# SCH_SEGEMENTOS.net
KiCad netlist of a schematic drawn in Altium Designer
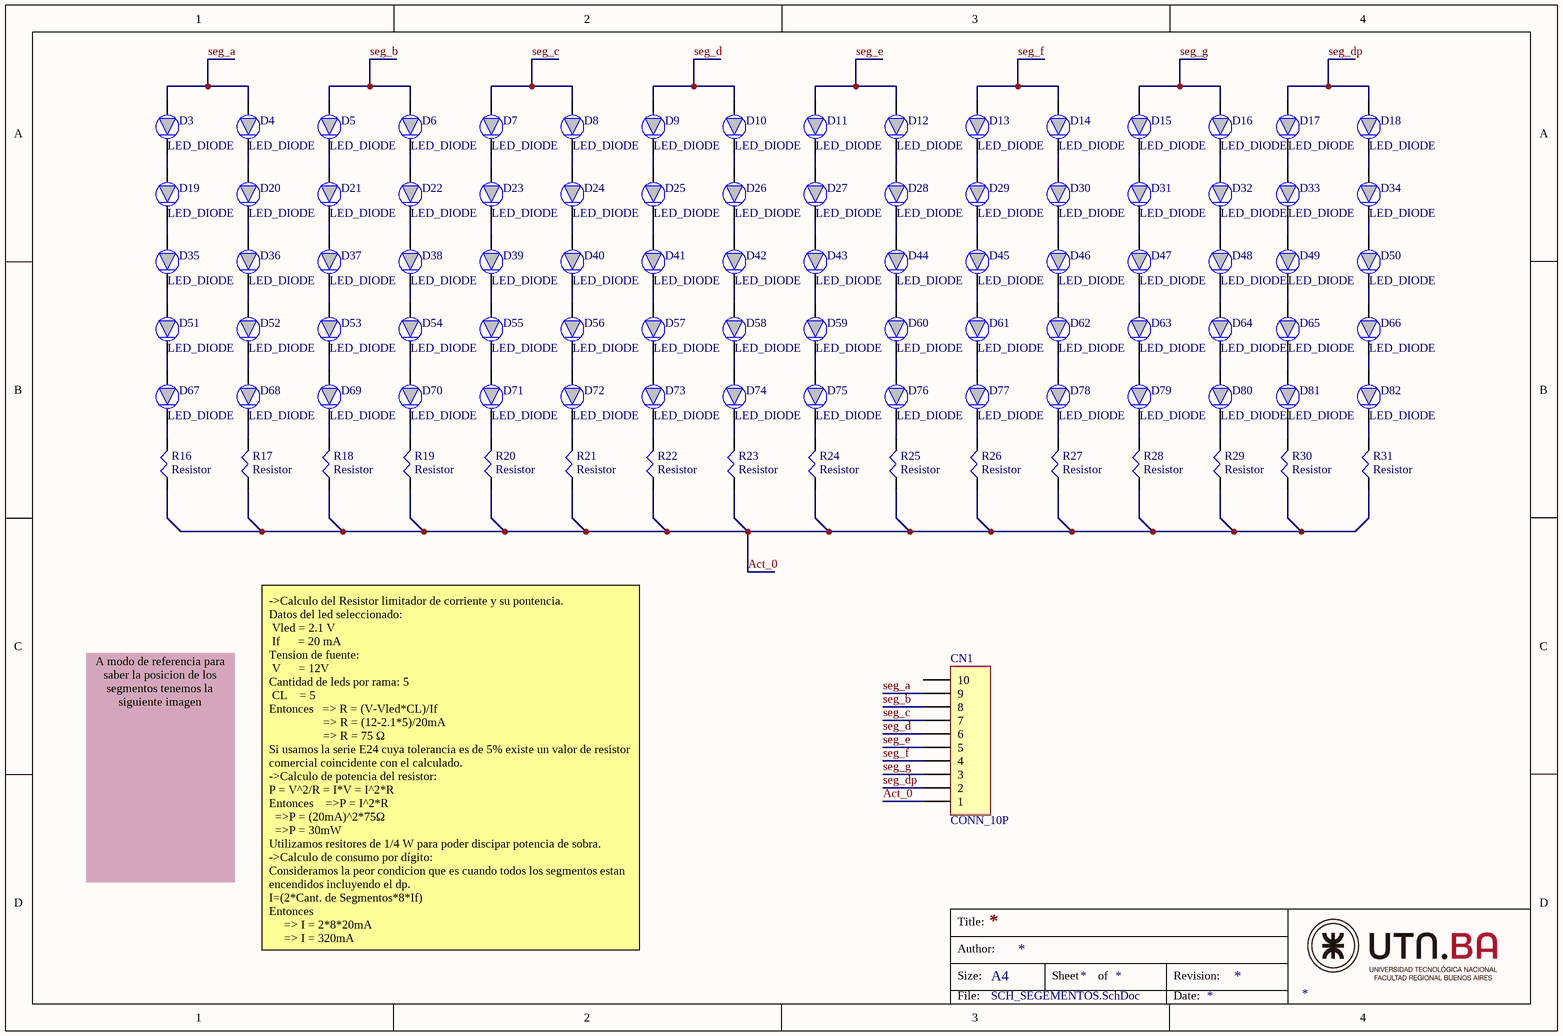
[diagram p0: SCH_SEGEMENTOS.SchDoc]

(export (version "E")
  (design (tool "Eeschema 10.0.6"))
  (components
    (comp (ref "CN1")
      (value "CONN_10P")
      (description "Connector Generic 10 Vias")
      (libsource (lib "SCH_LIB") (part "CONN_10P"))
    )
    (comp (ref "D3")
      (value "LED_DIODE")
      (description "LED rojo 0805")
      (libsource (lib "SCH_LIB") (part "LED_DIODE"))
    )
    (comp (ref "D4")
      (value "LED_DIODE")
      (description "LED rojo 0805")
      (libsource (lib "SCH_LIB") (part "LED_DIODE"))
    )
    (comp (ref "D5")
      (value "LED_DIODE")
      (description "LED rojo 0805")
      (libsource (lib "SCH_LIB") (part "LED_DIODE"))
    )
    (comp (ref "D6")
      (value "LED_DIODE")
      (description "LED rojo 0805")
      (libsource (lib "SCH_LIB") (part "LED_DIODE"))
    )
    (comp (ref "D7")
      (value "LED_DIODE")
      (description "LED rojo 0805")
      (libsource (lib "SCH_LIB") (part "LED_DIODE"))
    )
    (comp (ref "D8")
      (value "LED_DIODE")
      (description "LED rojo 0805")
      (libsource (lib "SCH_LIB") (part "LED_DIODE"))
    )
    (comp (ref "D9")
      (value "LED_DIODE")
      (description "LED rojo 0805")
      (libsource (lib "SCH_LIB") (part "LED_DIODE"))
    )
    (comp (ref "D10")
      (value "LED_DIODE")
      (description "LED rojo 0805")
      (libsource (lib "SCH_LIB") (part "LED_DIODE"))
    )
    (comp (ref "D11")
      (value "LED_DIODE")
      (description "LED rojo 0805")
      (libsource (lib "SCH_LIB") (part "LED_DIODE"))
    )
    (comp (ref "D12")
      (value "LED_DIODE")
      (description "LED rojo 0805")
      (libsource (lib "SCH_LIB") (part "LED_DIODE"))
    )
    (comp (ref "D13")
      (value "LED_DIODE")
      (description "LED rojo 0805")
      (libsource (lib "SCH_LIB") (part "LED_DIODE"))
    )
    (comp (ref "D14")
      (value "LED_DIODE")
      (description "LED rojo 0805")
      (libsource (lib "SCH_LIB") (part "LED_DIODE"))
    )
    (comp (ref "D15")
      (value "LED_DIODE")
      (description "LED rojo 0805")
      (libsource (lib "SCH_LIB") (part "LED_DIODE"))
    )
    (comp (ref "D16")
      (value "LED_DIODE")
      (description "LED rojo 0805")
      (libsource (lib "SCH_LIB") (part "LED_DIODE"))
    )
    (comp (ref "D17")
      (value "LED_DIODE")
      (description "LED rojo 0805")
      (libsource (lib "SCH_LIB") (part "LED_DIODE"))
    )
    (comp (ref "D18")
      (value "LED_DIODE")
      (description "LED rojo 0805")
      (libsource (lib "SCH_LIB") (part "LED_DIODE"))
    )
    (comp (ref "D19")
      (value "LED_DIODE")
      (description "LED rojo 0805")
      (libsource (lib "SCH_LIB") (part "LED_DIODE"))
    )
    (comp (ref "D20")
      (value "LED_DIODE")
      (description "LED rojo 0805")
      (libsource (lib "SCH_LIB") (part "LED_DIODE"))
    )
    (comp (ref "D21")
      (value "LED_DIODE")
      (description "LED rojo 0805")
      (libsource (lib "SCH_LIB") (part "LED_DIODE"))
    )
    (comp (ref "D22")
      (value "LED_DIODE")
      (description "LED rojo 0805")
      (libsource (lib "SCH_LIB") (part "LED_DIODE"))
    )
    (comp (ref "D23")
      (value "LED_DIODE")
      (description "LED rojo 0805")
      (libsource (lib "SCH_LIB") (part "LED_DIODE"))
    )
    (comp (ref "D24")
      (value "LED_DIODE")
      (description "LED rojo 0805")
      (libsource (lib "SCH_LIB") (part "LED_DIODE"))
    )
    (comp (ref "D25")
      (value "LED_DIODE")
      (description "LED rojo 0805")
      (libsource (lib "SCH_LIB") (part "LED_DIODE"))
    )
    (comp (ref "D26")
      (value "LED_DIODE")
      (description "LED rojo 0805")
      (libsource (lib "SCH_LIB") (part "LED_DIODE"))
    )
    (comp (ref "D27")
      (value "LED_DIODE")
      (description "LED rojo 0805")
      (libsource (lib "SCH_LIB") (part "LED_DIODE"))
    )
    (comp (ref "D28")
      (value "LED_DIODE")
      (description "LED rojo 0805")
      (libsource (lib "SCH_LIB") (part "LED_DIODE"))
    )
    (comp (ref "D29")
      (value "LED_DIODE")
      (description "LED rojo 0805")
      (libsource (lib "SCH_LIB") (part "LED_DIODE"))
    )
    (comp (ref "D30")
      (value "LED_DIODE")
      (description "LED rojo 0805")
      (libsource (lib "SCH_LIB") (part "LED_DIODE"))
    )
    (comp (ref "D31")
      (value "LED_DIODE")
      (description "LED rojo 0805")
      (libsource (lib "SCH_LIB") (part "LED_DIODE"))
    )
    (comp (ref "D32")
      (value "LED_DIODE")
      (description "LED rojo 0805")
      (libsource (lib "SCH_LIB") (part "LED_DIODE"))
    )
    (comp (ref "D33")
      (value "LED_DIODE")
      (description "LED rojo 0805")
      (libsource (lib "SCH_LIB") (part "LED_DIODE"))
    )
    (comp (ref "D34")
      (value "LED_DIODE")
      (description "LED rojo 0805")
      (libsource (lib "SCH_LIB") (part "LED_DIODE"))
    )
    (comp (ref "D35")
      (value "LED_DIODE")
      (description "LED rojo 0805")
      (libsource (lib "SCH_LIB") (part "LED_DIODE"))
    )
    (comp (ref "D36")
      (value "LED_DIODE")
      (description "LED rojo 0805")
      (libsource (lib "SCH_LIB") (part "LED_DIODE"))
    )
    (comp (ref "D37")
      (value "LED_DIODE")
      (description "LED rojo 0805")
      (libsource (lib "SCH_LIB") (part "LED_DIODE"))
    )
    (comp (ref "D38")
      (value "LED_DIODE")
      (description "LED rojo 0805")
      (libsource (lib "SCH_LIB") (part "LED_DIODE"))
    )
    (comp (ref "D39")
      (value "LED_DIODE")
      (description "LED rojo 0805")
      (libsource (lib "SCH_LIB") (part "LED_DIODE"))
    )
    (comp (ref "D40")
      (value "LED_DIODE")
      (description "LED rojo 0805")
      (libsource (lib "SCH_LIB") (part "LED_DIODE"))
    )
    (comp (ref "D41")
      (value "LED_DIODE")
      (description "LED rojo 0805")
      (libsource (lib "SCH_LIB") (part "LED_DIODE"))
    )
    (comp (ref "D42")
      (value "LED_DIODE")
      (description "LED rojo 0805")
      (libsource (lib "SCH_LIB") (part "LED_DIODE"))
    )
    (comp (ref "D43")
      (value "LED_DIODE")
      (description "LED rojo 0805")
      (libsource (lib "SCH_LIB") (part "LED_DIODE"))
    )
    (comp (ref "D44")
      (value "LED_DIODE")
      (description "LED rojo 0805")
      (libsource (lib "SCH_LIB") (part "LED_DIODE"))
    )
    (comp (ref "D45")
      (value "LED_DIODE")
      (description "LED rojo 0805")
      (libsource (lib "SCH_LIB") (part "LED_DIODE"))
    )
    (comp (ref "D46")
      (value "LED_DIODE")
      (description "LED rojo 0805")
      (libsource (lib "SCH_LIB") (part "LED_DIODE"))
    )
    (comp (ref "D47")
      (value "LED_DIODE")
      (description "LED rojo 0805")
      (libsource (lib "SCH_LIB") (part "LED_DIODE"))
    )
    (comp (ref "D48")
      (value "LED_DIODE")
      (description "LED rojo 0805")
      (libsource (lib "SCH_LIB") (part "LED_DIODE"))
    )
    (comp (ref "D49")
      (value "LED_DIODE")
      (description "LED rojo 0805")
      (libsource (lib "SCH_LIB") (part "LED_DIODE"))
    )
    (comp (ref "D50")
      (value "LED_DIODE")
      (description "LED rojo 0805")
      (libsource (lib "SCH_LIB") (part "LED_DIODE"))
    )
    (comp (ref "D51")
      (value "LED_DIODE")
      (description "LED rojo 0805")
      (libsource (lib "SCH_LIB") (part "LED_DIODE"))
    )
    (comp (ref "D52")
      (value "LED_DIODE")
      (description "LED rojo 0805")
      (libsource (lib "SCH_LIB") (part "LED_DIODE"))
    )
    (comp (ref "D53")
      (value "LED_DIODE")
      (description "LED rojo 0805")
      (libsource (lib "SCH_LIB") (part "LED_DIODE"))
    )
    (comp (ref "D54")
      (value "LED_DIODE")
      (description "LED rojo 0805")
      (libsource (lib "SCH_LIB") (part "LED_DIODE"))
    )
    (comp (ref "D55")
      (value "LED_DIODE")
      (description "LED rojo 0805")
      (libsource (lib "SCH_LIB") (part "LED_DIODE"))
    )
    (comp (ref "D56")
      (value "LED_DIODE")
      (description "LED rojo 0805")
      (libsource (lib "SCH_LIB") (part "LED_DIODE"))
    )
    (comp (ref "D57")
      (value "LED_DIODE")
      (description "LED rojo 0805")
      (libsource (lib "SCH_LIB") (part "LED_DIODE"))
    )
    (comp (ref "D58")
      (value "LED_DIODE")
      (description "LED rojo 0805")
      (libsource (lib "SCH_LIB") (part "LED_DIODE"))
    )
    (comp (ref "D59")
      (value "LED_DIODE")
      (description "LED rojo 0805")
      (libsource (lib "SCH_LIB") (part "LED_DIODE"))
    )
    (comp (ref "D60")
      (value "LED_DIODE")
      (description "LED rojo 0805")
      (libsource (lib "SCH_LIB") (part "LED_DIODE"))
    )
    (comp (ref "D61")
      (value "LED_DIODE")
      (description "LED rojo 0805")
      (libsource (lib "SCH_LIB") (part "LED_DIODE"))
    )
    (comp (ref "D62")
      (value "LED_DIODE")
      (description "LED rojo 0805")
      (libsource (lib "SCH_LIB") (part "LED_DIODE"))
    )
    (comp (ref "D63")
      (value "LED_DIODE")
      (description "LED rojo 0805")
      (libsource (lib "SCH_LIB") (part "LED_DIODE"))
    )
    (comp (ref "D64")
      (value "LED_DIODE")
      (description "LED rojo 0805")
      (libsource (lib "SCH_LIB") (part "LED_DIODE"))
    )
    (comp (ref "D65")
      (value "LED_DIODE")
      (description "LED rojo 0805")
      (libsource (lib "SCH_LIB") (part "LED_DIODE"))
    )
    (comp (ref "D66")
      (value "LED_DIODE")
      (description "LED rojo 0805")
      (libsource (lib "SCH_LIB") (part "LED_DIODE"))
    )
    (comp (ref "D67")
      (value "LED_DIODE")
      (description "LED rojo 0805")
      (libsource (lib "SCH_LIB") (part "LED_DIODE"))
    )
    (comp (ref "D68")
      (value "LED_DIODE")
      (description "LED rojo 0805")
      (libsource (lib "SCH_LIB") (part "LED_DIODE"))
    )
    (comp (ref "D69")
      (value "LED_DIODE")
      (description "LED rojo 0805")
      (libsource (lib "SCH_LIB") (part "LED_DIODE"))
    )
    (comp (ref "D70")
      (value "LED_DIODE")
      (description "LED rojo 0805")
      (libsource (lib "SCH_LIB") (part "LED_DIODE"))
    )
    (comp (ref "D71")
      (value "LED_DIODE")
      (description "LED rojo 0805")
      (libsource (lib "SCH_LIB") (part "LED_DIODE"))
    )
    (comp (ref "D72")
      (value "LED_DIODE")
      (description "LED rojo 0805")
      (libsource (lib "SCH_LIB") (part "LED_DIODE"))
    )
    (comp (ref "D73")
      (value "LED_DIODE")
      (description "LED rojo 0805")
      (libsource (lib "SCH_LIB") (part "LED_DIODE"))
    )
    (comp (ref "D74")
      (value "LED_DIODE")
      (description "LED rojo 0805")
      (libsource (lib "SCH_LIB") (part "LED_DIODE"))
    )
    (comp (ref "D75")
      (value "LED_DIODE")
      (description "LED rojo 0805")
      (libsource (lib "SCH_LIB") (part "LED_DIODE"))
    )
    (comp (ref "D76")
      (value "LED_DIODE")
      (description "LED rojo 0805")
      (libsource (lib "SCH_LIB") (part "LED_DIODE"))
    )
    (comp (ref "D77")
      (value "LED_DIODE")
      (description "LED rojo 0805")
      (libsource (lib "SCH_LIB") (part "LED_DIODE"))
    )
    (comp (ref "D78")
      (value "LED_DIODE")
      (description "LED rojo 0805")
      (libsource (lib "SCH_LIB") (part "LED_DIODE"))
    )
    (comp (ref "D79")
      (value "LED_DIODE")
      (description "LED rojo 0805")
      (libsource (lib "SCH_LIB") (part "LED_DIODE"))
    )
    (comp (ref "D80")
      (value "LED_DIODE")
      (description "LED rojo 0805")
      (libsource (lib "SCH_LIB") (part "LED_DIODE"))
    )
    (comp (ref "D81")
      (value "LED_DIODE")
      (description "LED rojo 0805")
      (libsource (lib "SCH_LIB") (part "LED_DIODE"))
    )
    (comp (ref "D82")
      (value "LED_DIODE")
      (description "LED rojo 0805")
      (libsource (lib "SCH_LIB") (part "LED_DIODE"))
    )
    (comp (ref "R16") (value "Resistor") (libsource (lib "SCH_LIB") (part "Resistor")))
    (comp (ref "R17") (value "Resistor") (libsource (lib "SCH_LIB") (part "Resistor")))
    (comp (ref "R18") (value "Resistor") (libsource (lib "SCH_LIB") (part "Resistor")))
    (comp (ref "R19") (value "Resistor") (libsource (lib "SCH_LIB") (part "Resistor")))
    (comp (ref "R20") (value "Resistor") (libsource (lib "SCH_LIB") (part "Resistor")))
    (comp (ref "R21") (value "Resistor") (libsource (lib "SCH_LIB") (part "Resistor")))
    (comp (ref "R22") (value "Resistor") (libsource (lib "SCH_LIB") (part "Resistor")))
    (comp (ref "R23") (value "Resistor") (libsource (lib "SCH_LIB") (part "Resistor")))
    (comp (ref "R24") (value "Resistor") (libsource (lib "SCH_LIB") (part "Resistor")))
    (comp (ref "R25") (value "Resistor") (libsource (lib "SCH_LIB") (part "Resistor")))
    (comp (ref "R26") (value "Resistor") (libsource (lib "SCH_LIB") (part "Resistor")))
    (comp (ref "R27") (value "Resistor") (libsource (lib "SCH_LIB") (part "Resistor")))
    (comp (ref "R28") (value "Resistor") (libsource (lib "SCH_LIB") (part "Resistor")))
    (comp (ref "R29") (value "Resistor") (libsource (lib "SCH_LIB") (part "Resistor")))
    (comp (ref "R30") (value "Resistor") (libsource (lib "SCH_LIB") (part "Resistor")))
    (comp (ref "R31") (value "Resistor") (libsource (lib "SCH_LIB") (part "Resistor")))
  )
  (nets
    (net (code "1") (name "/Act_0") (class "Default")
      (node (ref "CN1") (pin "1") (pinfunction "1_1") (pintype "passive"))
      (node (ref "R16") (pin "47") (pinfunction "47_47") (pintype "passive"))
      (node (ref "R17") (pin "47") (pinfunction "47_47") (pintype "passive"))
      (node (ref "R18") (pin "47") (pinfunction "47_47") (pintype "passive"))
      (node (ref "R19") (pin "47") (pinfunction "47_47") (pintype "passive"))
      (node (ref "R20") (pin "47") (pinfunction "47_47") (pintype "passive"))
      (node (ref "R21") (pin "47") (pinfunction "47_47") (pintype "passive"))
      (node (ref "R22") (pin "47") (pinfunction "47_47") (pintype "passive"))
      (node (ref "R23") (pin "47") (pinfunction "47_47") (pintype "passive"))
      (node (ref "R24") (pin "47") (pinfunction "47_47") (pintype "passive"))
      (node (ref "R25") (pin "47") (pinfunction "47_47") (pintype "passive"))
      (node (ref "R26") (pin "47") (pinfunction "47_47") (pintype "passive"))
      (node (ref "R27") (pin "47") (pinfunction "47_47") (pintype "passive"))
      (node (ref "R28") (pin "47") (pinfunction "47_47") (pintype "passive"))
      (node (ref "R29") (pin "47") (pinfunction "47_47") (pintype "passive"))
      (node (ref "R30") (pin "47") (pinfunction "47_47") (pintype "passive"))
      (node (ref "R31") (pin "47") (pinfunction "47_47") (pintype "passive"))
    )
    (net (code "2") (name "/seg_a") (class "Default")
      (node (ref "CN1") (pin "9") (pinfunction "9_9") (pintype "passive"))
      (node (ref "D3") (pin "12") (pinfunction "12_12") (pintype "passive"))
      (node (ref "D4") (pin "12") (pinfunction "12_12") (pintype "passive"))
    )
    (net (code "3") (name "/seg_b") (class "Default")
      (node (ref "CN1") (pin "8") (pinfunction "8_8") (pintype "passive"))
      (node (ref "D5") (pin "12") (pinfunction "12_12") (pintype "passive"))
      (node (ref "D6") (pin "12") (pinfunction "12_12") (pintype "passive"))
    )
    (net (code "4") (name "/seg_c") (class "Default")
      (node (ref "CN1") (pin "7") (pinfunction "7_7") (pintype "passive"))
      (node (ref "D7") (pin "12") (pinfunction "12_12") (pintype "passive"))
      (node (ref "D8") (pin "12") (pinfunction "12_12") (pintype "passive"))
    )
    (net (code "5") (name "/seg_d") (class "Default")
      (node (ref "CN1") (pin "6") (pinfunction "6_6") (pintype "passive"))
      (node (ref "D10") (pin "12") (pinfunction "12_12") (pintype "passive"))
      (node (ref "D9") (pin "12") (pinfunction "12_12") (pintype "passive"))
    )
    (net (code "6") (name "/seg_dp") (class "Default")
      (node (ref "CN1") (pin "2") (pinfunction "2_2") (pintype "passive"))
      (node (ref "D17") (pin "12") (pinfunction "12_12") (pintype "passive"))
      (node (ref "D18") (pin "12") (pinfunction "12_12") (pintype "passive"))
    )
    (net (code "7") (name "/seg_e") (class "Default")
      (node (ref "CN1") (pin "5") (pinfunction "5_5") (pintype "passive"))
      (node (ref "D11") (pin "12") (pinfunction "12_12") (pintype "passive"))
      (node (ref "D12") (pin "12") (pinfunction "12_12") (pintype "passive"))
    )
    (net (code "8") (name "/seg_f") (class "Default")
      (node (ref "CN1") (pin "4") (pinfunction "4_4") (pintype "passive"))
      (node (ref "D13") (pin "12") (pinfunction "12_12") (pintype "passive"))
      (node (ref "D14") (pin "12") (pinfunction "12_12") (pintype "passive"))
    )
    (net (code "9") (name "/seg_g") (class "Default")
      (node (ref "CN1") (pin "3") (pinfunction "3_3") (pintype "passive"))
      (node (ref "D15") (pin "12") (pinfunction "12_12") (pintype "passive"))
      (node (ref "D16") (pin "12") (pinfunction "12_12") (pintype "passive"))
    )
    (net (code "10") (name "Net-(D10-Pad11)") (class "Default")
      (node (ref "D10") (pin "11") (pinfunction "11_11") (pintype "passive"))
      (node (ref "D26") (pin "12") (pinfunction "12_12") (pintype "passive"))
    )
    (net (code "11") (name "Net-(D11-Pad11)") (class "Default")
      (node (ref "D11") (pin "11") (pinfunction "11_11") (pintype "passive"))
      (node (ref "D27") (pin "12") (pinfunction "12_12") (pintype "passive"))
    )
    (net (code "12") (name "Net-(D12-Pad11)") (class "Default")
      (node (ref "D12") (pin "11") (pinfunction "11_11") (pintype "passive"))
      (node (ref "D28") (pin "12") (pinfunction "12_12") (pintype "passive"))
    )
    (net (code "13") (name "Net-(D13-Pad11)") (class "Default")
      (node (ref "D13") (pin "11") (pinfunction "11_11") (pintype "passive"))
      (node (ref "D29") (pin "12") (pinfunction "12_12") (pintype "passive"))
    )
    (net (code "14") (name "Net-(D14-Pad11)") (class "Default")
      (node (ref "D14") (pin "11") (pinfunction "11_11") (pintype "passive"))
      (node (ref "D30") (pin "12") (pinfunction "12_12") (pintype "passive"))
    )
    (net (code "15") (name "Net-(D15-Pad11)") (class "Default")
      (node (ref "D15") (pin "11") (pinfunction "11_11") (pintype "passive"))
      (node (ref "D31") (pin "12") (pinfunction "12_12") (pintype "passive"))
    )
    (net (code "16") (name "Net-(D16-Pad11)") (class "Default")
      (node (ref "D16") (pin "11") (pinfunction "11_11") (pintype "passive"))
      (node (ref "D32") (pin "12") (pinfunction "12_12") (pintype "passive"))
    )
    (net (code "17") (name "Net-(D17-Pad11)") (class "Default")
      (node (ref "D17") (pin "11") (pinfunction "11_11") (pintype "passive"))
      (node (ref "D33") (pin "12") (pinfunction "12_12") (pintype "passive"))
    )
    (net (code "18") (name "Net-(D18-Pad11)") (class "Default")
      (node (ref "D18") (pin "11") (pinfunction "11_11") (pintype "passive"))
      (node (ref "D34") (pin "12") (pinfunction "12_12") (pintype "passive"))
    )
    (net (code "19") (name "Net-(D19-Pad11)") (class "Default")
      (node (ref "D19") (pin "11") (pinfunction "11_11") (pintype "passive"))
      (node (ref "D35") (pin "12") (pinfunction "12_12") (pintype "passive"))
    )
    (net (code "20") (name "Net-(D19-Pad12)") (class "Default")
      (node (ref "D19") (pin "12") (pinfunction "12_12") (pintype "passive"))
      (node (ref "D3") (pin "11") (pinfunction "11_11") (pintype "passive"))
    )
    (net (code "21") (name "Net-(D20-Pad11)") (class "Default")
      (node (ref "D20") (pin "11") (pinfunction "11_11") (pintype "passive"))
      (node (ref "D36") (pin "12") (pinfunction "12_12") (pintype "passive"))
    )
    (net (code "22") (name "Net-(D20-Pad12)") (class "Default")
      (node (ref "D20") (pin "12") (pinfunction "12_12") (pintype "passive"))
      (node (ref "D4") (pin "11") (pinfunction "11_11") (pintype "passive"))
    )
    (net (code "23") (name "Net-(D21-Pad11)") (class "Default")
      (node (ref "D21") (pin "11") (pinfunction "11_11") (pintype "passive"))
      (node (ref "D37") (pin "12") (pinfunction "12_12") (pintype "passive"))
    )
    (net (code "24") (name "Net-(D21-Pad12)") (class "Default")
      (node (ref "D21") (pin "12") (pinfunction "12_12") (pintype "passive"))
      (node (ref "D5") (pin "11") (pinfunction "11_11") (pintype "passive"))
    )
    (net (code "25") (name "Net-(D22-Pad11)") (class "Default")
      (node (ref "D22") (pin "11") (pinfunction "11_11") (pintype "passive"))
      (node (ref "D38") (pin "12") (pinfunction "12_12") (pintype "passive"))
    )
    (net (code "26") (name "Net-(D22-Pad12)") (class "Default")
      (node (ref "D22") (pin "12") (pinfunction "12_12") (pintype "passive"))
      (node (ref "D6") (pin "11") (pinfunction "11_11") (pintype "passive"))
    )
    (net (code "27") (name "Net-(D23-Pad11)") (class "Default")
      (node (ref "D23") (pin "11") (pinfunction "11_11") (pintype "passive"))
      (node (ref "D39") (pin "12") (pinfunction "12_12") (pintype "passive"))
    )
    (net (code "28") (name "Net-(D23-Pad12)") (class "Default")
      (node (ref "D23") (pin "12") (pinfunction "12_12") (pintype "passive"))
      (node (ref "D7") (pin "11") (pinfunction "11_11") (pintype "passive"))
    )
    (net (code "29") (name "Net-(D24-Pad11)") (class "Default")
      (node (ref "D24") (pin "11") (pinfunction "11_11") (pintype "passive"))
      (node (ref "D40") (pin "12") (pinfunction "12_12") (pintype "passive"))
    )
    (net (code "30") (name "Net-(D24-Pad12)") (class "Default")
      (node (ref "D24") (pin "12") (pinfunction "12_12") (pintype "passive"))
      (node (ref "D8") (pin "11") (pinfunction "11_11") (pintype "passive"))
    )
    (net (code "31") (name "Net-(D25-Pad11)") (class "Default")
      (node (ref "D25") (pin "11") (pinfunction "11_11") (pintype "passive"))
      (node (ref "D41") (pin "12") (pinfunction "12_12") (pintype "passive"))
    )
    (net (code "32") (name "Net-(D25-Pad12)") (class "Default")
      (node (ref "D25") (pin "12") (pinfunction "12_12") (pintype "passive"))
      (node (ref "D9") (pin "11") (pinfunction "11_11") (pintype "passive"))
    )
    (net (code "33") (name "Net-(D26-Pad11)") (class "Default")
      (node (ref "D26") (pin "11") (pinfunction "11_11") (pintype "passive"))
      (node (ref "D42") (pin "12") (pinfunction "12_12") (pintype "passive"))
    )
    (net (code "34") (name "Net-(D27-Pad11)") (class "Default")
      (node (ref "D27") (pin "11") (pinfunction "11_11") (pintype "passive"))
      (node (ref "D43") (pin "12") (pinfunction "12_12") (pintype "passive"))
    )
    (net (code "35") (name "Net-(D28-Pad11)") (class "Default")
      (node (ref "D28") (pin "11") (pinfunction "11_11") (pintype "passive"))
      (node (ref "D44") (pin "12") (pinfunction "12_12") (pintype "passive"))
    )
    (net (code "36") (name "Net-(D29-Pad11)") (class "Default")
      (node (ref "D29") (pin "11") (pinfunction "11_11") (pintype "passive"))
      (node (ref "D45") (pin "12") (pinfunction "12_12") (pintype "passive"))
    )
    (net (code "37") (name "Net-(D30-Pad11)") (class "Default")
      (node (ref "D30") (pin "11") (pinfunction "11_11") (pintype "passive"))
      (node (ref "D46") (pin "12") (pinfunction "12_12") (pintype "passive"))
    )
    (net (code "38") (name "Net-(D31-Pad11)") (class "Default")
      (node (ref "D31") (pin "11") (pinfunction "11_11") (pintype "passive"))
      (node (ref "D47") (pin "12") (pinfunction "12_12") (pintype "passive"))
    )
    (net (code "39") (name "Net-(D32-Pad11)") (class "Default")
      (node (ref "D32") (pin "11") (pinfunction "11_11") (pintype "passive"))
      (node (ref "D48") (pin "12") (pinfunction "12_12") (pintype "passive"))
    )
    (net (code "40") (name "Net-(D33-Pad11)") (class "Default")
      (node (ref "D33") (pin "11") (pinfunction "11_11") (pintype "passive"))
      (node (ref "D49") (pin "12") (pinfunction "12_12") (pintype "passive"))
    )
    (net (code "41") (name "Net-(D34-Pad11)") (class "Default")
      (node (ref "D34") (pin "11") (pinfunction "11_11") (pintype "passive"))
      (node (ref "D50") (pin "12") (pinfunction "12_12") (pintype "passive"))
    )
    (net (code "42") (name "Net-(D35-Pad11)") (class "Default")
      (node (ref "D35") (pin "11") (pinfunction "11_11") (pintype "passive"))
      (node (ref "D51") (pin "12") (pinfunction "12_12") (pintype "passive"))
    )
    (net (code "43") (name "Net-(D36-Pad11)") (class "Default")
      (node (ref "D36") (pin "11") (pinfunction "11_11") (pintype "passive"))
      (node (ref "D52") (pin "12") (pinfunction "12_12") (pintype "passive"))
    )
    (net (code "44") (name "Net-(D37-Pad11)") (class "Default")
      (node (ref "D37") (pin "11") (pinfunction "11_11") (pintype "passive"))
      (node (ref "D53") (pin "12") (pinfunction "12_12") (pintype "passive"))
    )
    (net (code "45") (name "Net-(D38-Pad11)") (class "Default")
      (node (ref "D38") (pin "11") (pinfunction "11_11") (pintype "passive"))
      (node (ref "D54") (pin "12") (pinfunction "12_12") (pintype "passive"))
    )
    (net (code "46") (name "Net-(D39-Pad11)") (class "Default")
      (node (ref "D39") (pin "11") (pinfunction "11_11") (pintype "passive"))
      (node (ref "D55") (pin "12") (pinfunction "12_12") (pintype "passive"))
    )
    (net (code "47") (name "Net-(D40-Pad11)") (class "Default")
      (node (ref "D40") (pin "11") (pinfunction "11_11") (pintype "passive"))
      (node (ref "D56") (pin "12") (pinfunction "12_12") (pintype "passive"))
    )
    (net (code "48") (name "Net-(D41-Pad11)") (class "Default")
      (node (ref "D41") (pin "11") (pinfunction "11_11") (pintype "passive"))
      (node (ref "D57") (pin "12") (pinfunction "12_12") (pintype "passive"))
    )
    (net (code "49") (name "Net-(D42-Pad11)") (class "Default")
      (node (ref "D42") (pin "11") (pinfunction "11_11") (pintype "passive"))
      (node (ref "D58") (pin "12") (pinfunction "12_12") (pintype "passive"))
    )
    (net (code "50") (name "Net-(D43-Pad11)") (class "Default")
      (node (ref "D43") (pin "11") (pinfunction "11_11") (pintype "passive"))
      (node (ref "D59") (pin "12") (pinfunction "12_12") (pintype "passive"))
    )
    (net (code "51") (name "Net-(D44-Pad11)") (class "Default")
      (node (ref "D44") (pin "11") (pinfunction "11_11") (pintype "passive"))
      (node (ref "D60") (pin "12") (pinfunction "12_12") (pintype "passive"))
    )
    (net (code "52") (name "Net-(D45-Pad11)") (class "Default")
      (node (ref "D45") (pin "11") (pinfunction "11_11") (pintype "passive"))
      (node (ref "D61") (pin "12") (pinfunction "12_12") (pintype "passive"))
    )
    (net (code "53") (name "Net-(D46-Pad11)") (class "Default")
      (node (ref "D46") (pin "11") (pinfunction "11_11") (pintype "passive"))
      (node (ref "D62") (pin "12") (pinfunction "12_12") (pintype "passive"))
    )
    (net (code "54") (name "Net-(D47-Pad11)") (class "Default")
      (node (ref "D47") (pin "11") (pinfunction "11_11") (pintype "passive"))
      (node (ref "D63") (pin "12") (pinfunction "12_12") (pintype "passive"))
    )
    (net (code "55") (name "Net-(D48-Pad11)") (class "Default")
      (node (ref "D48") (pin "11") (pinfunction "11_11") (pintype "passive"))
      (node (ref "D64") (pin "12") (pinfunction "12_12") (pintype "passive"))
    )
    (net (code "56") (name "Net-(D49-Pad11)") (class "Default")
      (node (ref "D49") (pin "11") (pinfunction "11_11") (pintype "passive"))
      (node (ref "D65") (pin "12") (pinfunction "12_12") (pintype "passive"))
    )
    (net (code "57") (name "Net-(D50-Pad11)") (class "Default")
      (node (ref "D50") (pin "11") (pinfunction "11_11") (pintype "passive"))
      (node (ref "D66") (pin "12") (pinfunction "12_12") (pintype "passive"))
    )
    (net (code "58") (name "Net-(D51-Pad11)") (class "Default")
      (node (ref "D51") (pin "11") (pinfunction "11_11") (pintype "passive"))
      (node (ref "D67") (pin "12") (pinfunction "12_12") (pintype "passive"))
    )
    (net (code "59") (name "Net-(D52-Pad11)") (class "Default")
      (node (ref "D52") (pin "11") (pinfunction "11_11") (pintype "passive"))
      (node (ref "D68") (pin "12") (pinfunction "12_12") (pintype "passive"))
    )
    (net (code "60") (name "Net-(D53-Pad11)") (class "Default")
      (node (ref "D53") (pin "11") (pinfunction "11_11") (pintype "passive"))
      (node (ref "D69") (pin "12") (pinfunction "12_12") (pintype "passive"))
    )
    (net (code "61") (name "Net-(D54-Pad11)") (class "Default")
      (node (ref "D54") (pin "11") (pinfunction "11_11") (pintype "passive"))
      (node (ref "D70") (pin "12") (pinfunction "12_12") (pintype "passive"))
    )
    (net (code "62") (name "Net-(D55-Pad11)") (class "Default")
      (node (ref "D55") (pin "11") (pinfunction "11_11") (pintype "passive"))
      (node (ref "D71") (pin "12") (pinfunction "12_12") (pintype "passive"))
    )
    (net (code "63") (name "Net-(D56-Pad11)") (class "Default")
      (node (ref "D56") (pin "11") (pinfunction "11_11") (pintype "passive"))
      (node (ref "D72") (pin "12") (pinfunction "12_12") (pintype "passive"))
    )
    (net (code "64") (name "Net-(D57-Pad11)") (class "Default")
      (node (ref "D57") (pin "11") (pinfunction "11_11") (pintype "passive"))
      (node (ref "D73") (pin "12") (pinfunction "12_12") (pintype "passive"))
    )
    (net (code "65") (name "Net-(D58-Pad11)") (class "Default")
      (node (ref "D58") (pin "11") (pinfunction "11_11") (pintype "passive"))
      (node (ref "D74") (pin "12") (pinfunction "12_12") (pintype "passive"))
    )
    (net (code "66") (name "Net-(D59-Pad11)") (class "Default")
      (node (ref "D59") (pin "11") (pinfunction "11_11") (pintype "passive"))
      (node (ref "D75") (pin "12") (pinfunction "12_12") (pintype "passive"))
    )
    (net (code "67") (name "Net-(D60-Pad11)") (class "Default")
      (node (ref "D60") (pin "11") (pinfunction "11_11") (pintype "passive"))
      (node (ref "D76") (pin "12") (pinfunction "12_12") (pintype "passive"))
    )
    (net (code "68") (name "Net-(D61-Pad11)") (class "Default")
      (node (ref "D61") (pin "11") (pinfunction "11_11") (pintype "passive"))
      (node (ref "D77") (pin "12") (pinfunction "12_12") (pintype "passive"))
    )
    (net (code "69") (name "Net-(D62-Pad11)") (class "Default")
      (node (ref "D62") (pin "11") (pinfunction "11_11") (pintype "passive"))
      (node (ref "D78") (pin "12") (pinfunction "12_12") (pintype "passive"))
    )
    (net (code "70") (name "Net-(D63-Pad11)") (class "Default")
      (node (ref "D63") (pin "11") (pinfunction "11_11") (pintype "passive"))
      (node (ref "D79") (pin "12") (pinfunction "12_12") (pintype "passive"))
    )
    (net (code "71") (name "Net-(D64-Pad11)") (class "Default")
      (node (ref "D64") (pin "11") (pinfunction "11_11") (pintype "passive"))
      (node (ref "D80") (pin "12") (pinfunction "12_12") (pintype "passive"))
    )
    (net (code "72") (name "Net-(D65-Pad11)") (class "Default")
      (node (ref "D65") (pin "11") (pinfunction "11_11") (pintype "passive"))
      (node (ref "D81") (pin "12") (pinfunction "12_12") (pintype "passive"))
    )
    (net (code "73") (name "Net-(D66-Pad11)") (class "Default")
      (node (ref "D66") (pin "11") (pinfunction "11_11") (pintype "passive"))
      (node (ref "D82") (pin "12") (pinfunction "12_12") (pintype "passive"))
    )
    (net (code "74") (name "Net-(D67-Pad11)") (class "Default")
      (node (ref "D67") (pin "11") (pinfunction "11_11") (pintype "passive"))
      (node (ref "R16") (pin "48") (pinfunction "48_48") (pintype "passive"))
    )
    (net (code "75") (name "Net-(D68-Pad11)") (class "Default")
      (node (ref "D68") (pin "11") (pinfunction "11_11") (pintype "passive"))
      (node (ref "R17") (pin "48") (pinfunction "48_48") (pintype "passive"))
    )
    (net (code "76") (name "Net-(D69-Pad11)") (class "Default")
      (node (ref "D69") (pin "11") (pinfunction "11_11") (pintype "passive"))
      (node (ref "R18") (pin "48") (pinfunction "48_48") (pintype "passive"))
    )
    (net (code "77") (name "Net-(D70-Pad11)") (class "Default")
      (node (ref "D70") (pin "11") (pinfunction "11_11") (pintype "passive"))
      (node (ref "R19") (pin "48") (pinfunction "48_48") (pintype "passive"))
    )
    (net (code "78") (name "Net-(D71-Pad11)") (class "Default")
      (node (ref "D71") (pin "11") (pinfunction "11_11") (pintype "passive"))
      (node (ref "R20") (pin "48") (pinfunction "48_48") (pintype "passive"))
    )
    (net (code "79") (name "Net-(D72-Pad11)") (class "Default")
      (node (ref "D72") (pin "11") (pinfunction "11_11") (pintype "passive"))
      (node (ref "R21") (pin "48") (pinfunction "48_48") (pintype "passive"))
    )
    (net (code "80") (name "Net-(D73-Pad11)") (class "Default")
      (node (ref "D73") (pin "11") (pinfunction "11_11") (pintype "passive"))
      (node (ref "R22") (pin "48") (pinfunction "48_48") (pintype "passive"))
    )
    (net (code "81") (name "Net-(D74-Pad11)") (class "Default")
      (node (ref "D74") (pin "11") (pinfunction "11_11") (pintype "passive"))
      (node (ref "R23") (pin "48") (pinfunction "48_48") (pintype "passive"))
    )
    (net (code "82") (name "Net-(D75-Pad11)") (class "Default")
      (node (ref "D75") (pin "11") (pinfunction "11_11") (pintype "passive"))
      (node (ref "R24") (pin "48") (pinfunction "48_48") (pintype "passive"))
    )
    (net (code "83") (name "Net-(D76-Pad11)") (class "Default")
      (node (ref "D76") (pin "11") (pinfunction "11_11") (pintype "passive"))
      (node (ref "R25") (pin "48") (pinfunction "48_48") (pintype "passive"))
    )
    (net (code "84") (name "Net-(D77-Pad11)") (class "Default")
      (node (ref "D77") (pin "11") (pinfunction "11_11") (pintype "passive"))
      (node (ref "R26") (pin "48") (pinfunction "48_48") (pintype "passive"))
    )
    (net (code "85") (name "Net-(D78-Pad11)") (class "Default")
      (node (ref "D78") (pin "11") (pinfunction "11_11") (pintype "passive"))
      (node (ref "R27") (pin "48") (pinfunction "48_48") (pintype "passive"))
    )
    (net (code "86") (name "Net-(D79-Pad11)") (class "Default")
      (node (ref "D79") (pin "11") (pinfunction "11_11") (pintype "passive"))
      (node (ref "R28") (pin "48") (pinfunction "48_48") (pintype "passive"))
    )
    (net (code "87") (name "Net-(D80-Pad11)") (class "Default")
      (node (ref "D80") (pin "11") (pinfunction "11_11") (pintype "passive"))
      (node (ref "R29") (pin "48") (pinfunction "48_48") (pintype "passive"))
    )
    (net (code "88") (name "Net-(D81-Pad11)") (class "Default")
      (node (ref "D81") (pin "11") (pinfunction "11_11") (pintype "passive"))
      (node (ref "R30") (pin "48") (pinfunction "48_48") (pintype "passive"))
    )
    (net (code "89") (name "Net-(D82-Pad11)") (class "Default")
      (node (ref "D82") (pin "11") (pinfunction "11_11") (pintype "passive"))
      (node (ref "R31") (pin "48") (pinfunction "48_48") (pintype "passive"))
    )
    (net (code "90") (name "unconnected-(CN1-Pad10)") (class "Default")
      (node (ref "CN1") (pin "10") (pinfunction "10_10") (pintype "passive"))
    )
  )
)
